# ltc6655LS8_reference_module.net
KiCad netlist of a schematic drawn in EAGLE
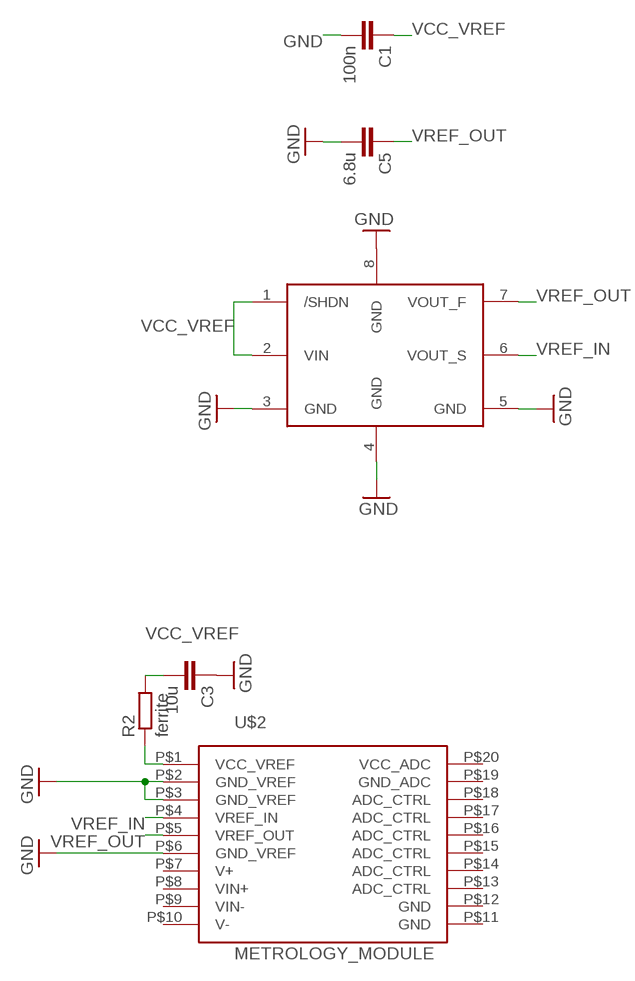
[diagram p0: schematic, sheet 1]

(export (version "E")
  (design (tool "Eeschema 10.0.6"))
  (components
    (comp (ref "C1")
      (value "100n")
      (footprint "eagle-import:C0603")
      (libsource (lib "eagle-import") (part "C-EUC0603"))
    )
    (comp (ref "C3")
      (value "10u")
      (footprint "eagle-import:C0805")
      (libsource (lib "eagle-import") (part "C-EUC0805"))
    )
    (comp (ref "C5")
      (value "6.8u")
      (footprint "eagle-import:C050-085X075W")
      (libsource (lib "eagle-import") (part "C-EU050-085X075W"))
    )
    (comp (ref "R2")
      (value "ferrite")
      (footprint "eagle-import:R0805")
      (libsource (lib "eagle-import") (part "R-EU_R0805"))
    )
    (comp (ref "U$1")
      (value "LTC6655LS8_ELONG")
      (footprint "eagle-import:LS8_ELONG")
      (libsource (lib "eagle-import") (part "LTC6655LS8_ELONG"))
    )
    (comp (ref "U$2")
      (value "METROLOGY_MODULE")
      (footprint "eagle-import:METROLOGY_MODULE")
      (libsource (lib "eagle-import") (part "METROLOGY_MODULE"))
    )
  )
  (nets
    (net (code "1") (name "/VCC_VREF") (class "Default")
      (node (ref "C1") (pin "1") (pinfunction "1_1") (pintype "passive"))
      (node (ref "C3") (pin "2") (pinfunction "2_2") (pintype "passive"))
      (node (ref "R2") (pin "2") (pinfunction "2_2") (pintype "passive"))
      (node (ref "U$1") (pin "1") (pinfunction "/SHDN_1") (pintype "input"))
      (node (ref "U$1") (pin "2") (pinfunction "VIN_2") (pintype "input"))
    )
    (net (code "2") (name "/VREF_IN") (class "Default")
      (node (ref "U$1") (pin "6") (pinfunction "VOUT_S_6") (pintype "input"))
      (node (ref "U$2") (pin "P$4") (pinfunction "VREF_IN_P$4") (pintype "bidirectional"))
    )
    (net (code "3") (name "/VREF_OUT") (class "Default")
      (node (ref "C5") (pin "1") (pinfunction "1_1") (pintype "passive"))
      (node (ref "U$1") (pin "7") (pinfunction "VOUT_F_7") (pintype "input"))
      (node (ref "U$2") (pin "P$5") (pinfunction "VREF_OUT_P$5") (pintype "bidirectional"))
    )
    (net (code "4") (name "GND") (class "Default")
      (node (ref "C1") (pin "2") (pinfunction "2_2") (pintype "passive"))
      (node (ref "C3") (pin "1") (pinfunction "1_1") (pintype "passive"))
      (node (ref "C5") (pin "2") (pinfunction "2_2") (pintype "passive"))
      (node (ref "U$1") (pin "3") (pinfunction "GND_3") (pintype "input"))
      (node (ref "U$1") (pin "4") (pinfunction "GND_4") (pintype "input"))
      (node (ref "U$1") (pin "5") (pinfunction "GND_5") (pintype "input"))
      (node (ref "U$1") (pin "8") (pinfunction "GND_8") (pintype "input"))
      (node (ref "U$2") (pin "P$2") (pinfunction "GND_VREF_P$2") (pintype "bidirectional"))
      (node (ref "U$2") (pin "P$3") (pinfunction "GND_VREF_P$3") (pintype "bidirectional"))
      (node (ref "U$2") (pin "P$6") (pinfunction "GND_VREF_P$6") (pintype "bidirectional"))
    )
    (net (code "5") (name "Net-(U$2-VCC_VREF)") (class "Default")
      (node (ref "R2") (pin "1") (pinfunction "1_1") (pintype "passive"))
      (node (ref "U$2") (pin "P$1") (pinfunction "VCC_VREF_P$1") (pintype "bidirectional"))
    )
    (net (code "6") (name "unconnected-(U$2-ADC_CTRL-PadP$13)") (class "Default")
      (node (ref "U$2") (pin "P$13") (pinfunction "ADC_CTRL_P$13") (pintype "bidirectional"))
    )
    (net (code "7") (name "unconnected-(U$2-ADC_CTRL-PadP$14)") (class "Default")
      (node (ref "U$2") (pin "P$14") (pinfunction "ADC_CTRL_P$14") (pintype "bidirectional"))
    )
    (net (code "8") (name "unconnected-(U$2-ADC_CTRL-PadP$15)") (class "Default")
      (node (ref "U$2") (pin "P$15") (pinfunction "ADC_CTRL_P$15") (pintype "bidirectional"))
    )
    (net (code "9") (name "unconnected-(U$2-ADC_CTRL-PadP$16)") (class "Default")
      (node (ref "U$2") (pin "P$16") (pinfunction "ADC_CTRL_P$16") (pintype "bidirectional"))
    )
    (net (code "10") (name "unconnected-(U$2-ADC_CTRL-PadP$17)") (class "Default")
      (node (ref "U$2") (pin "P$17") (pinfunction "ADC_CTRL_P$17") (pintype "bidirectional"))
    )
    (net (code "11") (name "unconnected-(U$2-ADC_CTRL-PadP$18)") (class "Default")
      (node (ref "U$2") (pin "P$18") (pinfunction "ADC_CTRL_P$18") (pintype "bidirectional"))
    )
    (net (code "12") (name "unconnected-(U$2-GND-PadP$11)") (class "Default")
      (node (ref "U$2") (pin "P$11") (pinfunction "GND_P$11") (pintype "bidirectional"))
    )
    (net (code "13") (name "unconnected-(U$2-GND-PadP$12)") (class "Default")
      (node (ref "U$2") (pin "P$12") (pinfunction "GND_P$12") (pintype "bidirectional"))
    )
    (net (code "14") (name "unconnected-(U$2-GND_ADC-PadP$19)") (class "Default")
      (node (ref "U$2") (pin "P$19") (pinfunction "GND_ADC_P$19") (pintype "bidirectional"))
    )
    (net (code "15") (name "unconnected-(U$2-V+-PadP$7)") (class "Default")
      (node (ref "U$2") (pin "P$7") (pinfunction "V+_P$7") (pintype "bidirectional"))
    )
    (net (code "16") (name "unconnected-(U$2-V--PadP$10)") (class "Default")
      (node (ref "U$2") (pin "P$10") (pinfunction "V-_P$10") (pintype "bidirectional"))
    )
    (net (code "17") (name "unconnected-(U$2-VCC_ADC-PadP$20)") (class "Default")
      (node (ref "U$2") (pin "P$20") (pinfunction "VCC_ADC_P$20") (pintype "bidirectional"))
    )
    (net (code "18") (name "unconnected-(U$2-VIN+-PadP$8)") (class "Default")
      (node (ref "U$2") (pin "P$8") (pinfunction "VIN+_P$8") (pintype "bidirectional"))
    )
    (net (code "19") (name "unconnected-(U$2-VIN--PadP$9)") (class "Default")
      (node (ref "U$2") (pin "P$9") (pinfunction "VIN-_P$9") (pintype "bidirectional"))
    )
  )
)
